# Sheet1.net
KiCad netlist of a schematic drawn in Altium Designer
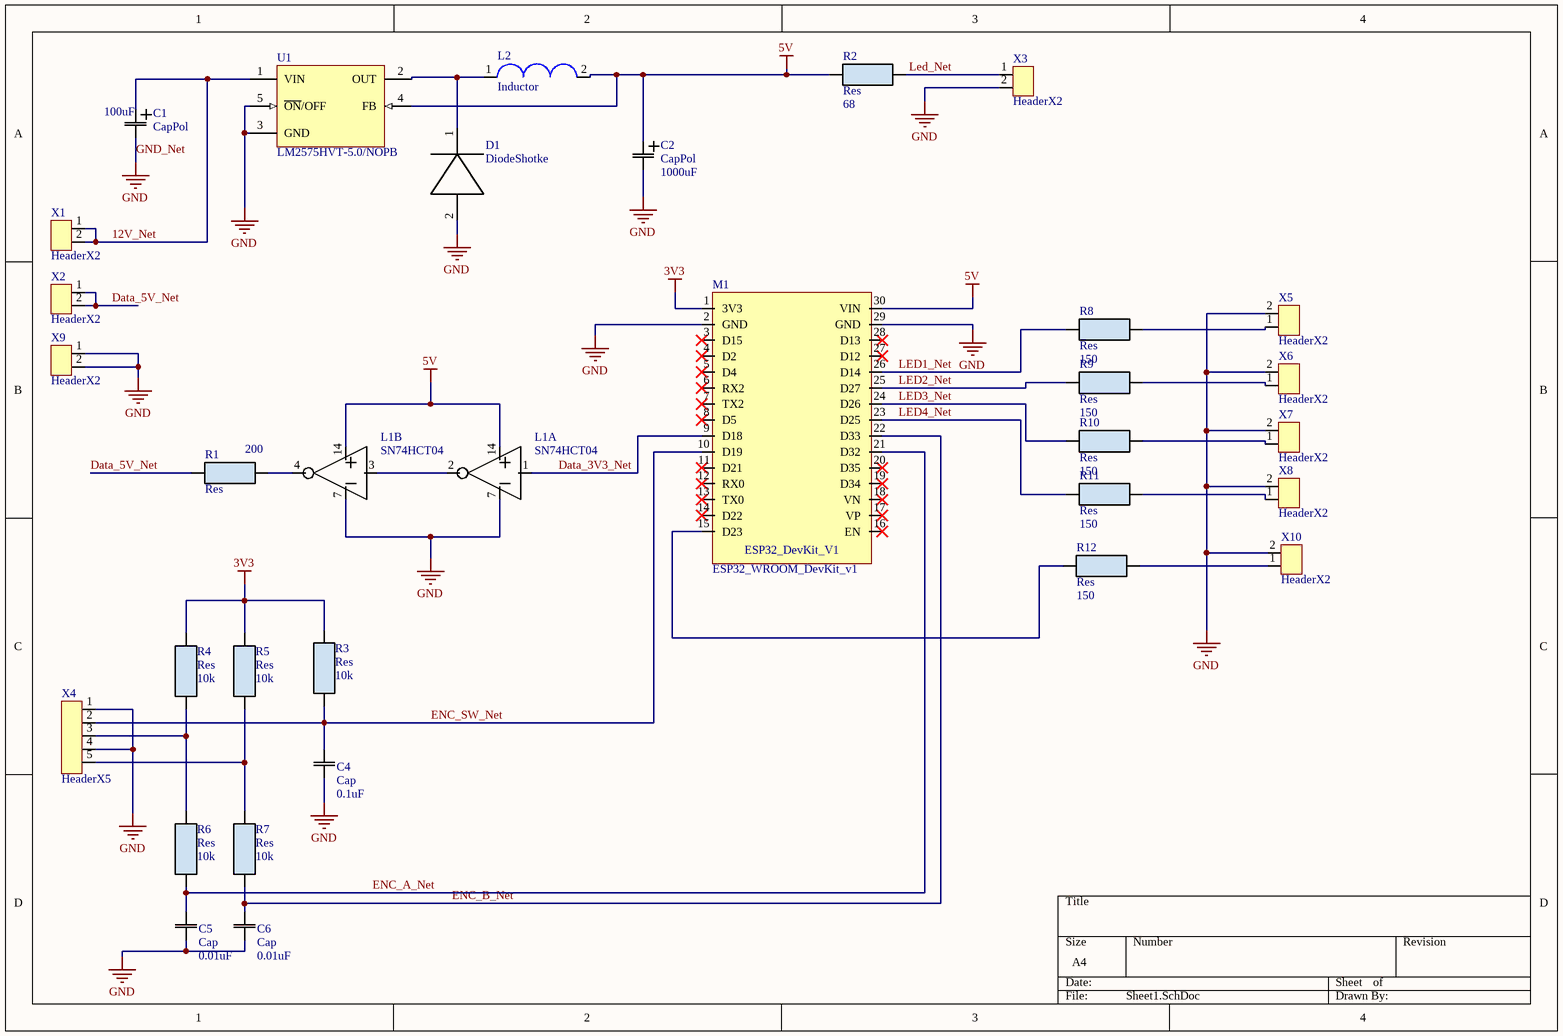
[diagram p0: Sheet1.SchDoc]

(export (version "E")
  (design (tool "Eeschema 10.0.6"))
  (components
    (comp (ref "C1")
      (value "CapPol")
      (footprint "CAP 8x7")
      (fields (field (name "ALTIUM_VALUE") "100uF"))
      (libsource (lib "KiShiVi") (part "CapPol"))
    )
    (comp (ref "C2")
      (value "CapPol")
      (footprint "CAP 10x12.5")
      (fields (field (name "ALTIUM_VALUE") "1000uF"))
      (libsource (lib "KiShiVi") (part "CapPol"))
    )
    (comp (ref "C4")
      (value "Cap")
      (footprint "Cap K73-17 0.1uF 100V 5-10%")
      (fields (field (name "ALTIUM_VALUE") "0.1uF"))
      (libsource (lib "KiShiVi") (part "Cap"))
    )
    (comp (ref "C5")
      (value "Cap")
      (footprint "Cap K73-17 0.01uF 100V 5-10%")
      (fields (field (name "ALTIUM_VALUE") "0.01uF"))
      (libsource (lib "KiShiVi") (part "Cap"))
    )
    (comp (ref "C6")
      (value "Cap")
      (footprint "Cap K73-17 0.01uF 100V 5-10%")
      (fields (field (name "ALTIUM_VALUE") "0.01uF"))
      (libsource (lib "KiShiVi") (part "Cap"))
    )
    (comp (ref "D1")
      (value "DiodeShotke")
      (footprint "DIODE_SHOTKE")
      (libsource (lib "KiShiVi") (part "DiodeShotke"))
    )
    (comp (ref "L1") (value "SN74HCT04") (footprint "DIP-14") (libsource (lib "KiShiVi") (part "SN74HCT04")))
    (comp (ref "L2")
      (value "Inductor")
      (footprint "RLB0912-101KL")
      (libsource (lib "KiShiVi") (part "Inductor"))
    )
    (comp (ref "M1")
      (value "ESP32_WROOM_DevKit_v1")
      (footprint "ESP32_WROOM_DevKit_v1")
      (libsource (lib "KiShiVi") (part "ESP32_WROOM_DevKit_v1"))
    )
    (comp (ref "R1")
      (value "Res")
      (footprint "Resistor MF-25")
      (fields (field (name "ALTIUM_VALUE") "200"))
      (libsource (lib "") (part "Res_1"))
    )
    (comp (ref "R2")
      (value "Res")
      (footprint "Resistor MF-25")
      (fields (field (name "ALTIUM_VALUE") "68"))
      (libsource (lib "") (part "Res_1"))
    )
    (comp (ref "R3")
      (value "Res")
      (footprint "Resistor MF-25")
      (fields (field (name "ALTIUM_VALUE") "10k"))
      (libsource (lib "KiShiVi") (part "Res"))
    )
    (comp (ref "R4")
      (value "Res")
      (footprint "Resistor MF-25")
      (fields (field (name "ALTIUM_VALUE") "10k"))
      (libsource (lib "KiShiVi") (part "Res"))
    )
    (comp (ref "R5")
      (value "Res")
      (footprint "Resistor MF-25")
      (fields (field (name "ALTIUM_VALUE") "10k"))
      (libsource (lib "KiShiVi") (part "Res"))
    )
    (comp (ref "R6")
      (value "Res")
      (footprint "Resistor MF-25")
      (fields (field (name "ALTIUM_VALUE") "10k"))
      (libsource (lib "KiShiVi") (part "Res"))
    )
    (comp (ref "R7")
      (value "Res")
      (footprint "Resistor MF-25")
      (fields (field (name "ALTIUM_VALUE") "10k"))
      (libsource (lib "KiShiVi") (part "Res"))
    )
    (comp (ref "R8")
      (value "Res")
      (footprint "Resistor MF-25")
      (fields (field (name "ALTIUM_VALUE") "150"))
      (libsource (lib "") (part "Res_1"))
    )
    (comp (ref "R9")
      (value "Res")
      (footprint "Resistor MF-25")
      (fields (field (name "ALTIUM_VALUE") "150"))
      (libsource (lib "") (part "Res_1"))
    )
    (comp (ref "R10")
      (value "Res")
      (footprint "Resistor MF-25")
      (fields (field (name "ALTIUM_VALUE") "150"))
      (libsource (lib "") (part "Res_1"))
    )
    (comp (ref "R11")
      (value "Res")
      (footprint "Resistor MF-25")
      (fields (field (name "ALTIUM_VALUE") "150"))
      (libsource (lib "") (part "Res_1"))
    )
    (comp (ref "R12")
      (value "Res")
      (footprint "Resistor MF-25")
      (fields (field (name "ALTIUM_VALUE") "150"))
      (libsource (lib "") (part "Res_1"))
    )
    (comp (ref "U1")
      (value "LM2575HVT-5.0/NOPB")
      (footprint "KC0005A")
      (description "SIMPLE SWITCHER® 1A Step-Down Voltage Regulator, 5-pin TO-220, Pb-Free")
      (fields (field (name "MANUFACTURER") "Texas Instruments"))
      (libsource (lib "Altium Content Vault") (part "PM-REG-LM2575HVT-12"))
    )
    (comp (ref "X1")
      (value "HeaderX2")
      (footprint "TERMINAL_X2_5MM")
      (libsource (lib "") (part "HeaderX2_2"))
    )
    (comp (ref "X2")
      (value "HeaderX2")
      (footprint "TERMINAL_X2_5MM")
      (libsource (lib "") (part "HeaderX2_2"))
    )
    (comp (ref "X3") (value "HeaderX2") (footprint "HEADERX2") (libsource (lib "") (part "HeaderX2_1")))
    (comp (ref "X4") (value "HeaderX5") (footprint "HeaderX5") (libsource (lib "KiShiVi") (part "HeaderX5")))
    (comp (ref "X5") (value "HeaderX2") (footprint "HEADERX2") (libsource (lib "KiShiVi") (part "HeaderX2")))
    (comp (ref "X6") (value "HeaderX2") (footprint "HEADERX2") (libsource (lib "KiShiVi") (part "HeaderX2")))
    (comp (ref "X7") (value "HeaderX2") (footprint "HEADERX2") (libsource (lib "KiShiVi") (part "HeaderX2")))
    (comp (ref "X8") (value "HeaderX2") (footprint "HEADERX2") (libsource (lib "KiShiVi") (part "HeaderX2")))
    (comp (ref "X9")
      (value "HeaderX2")
      (footprint "TERMINAL_X2_5MM")
      (libsource (lib "") (part "HeaderX2_2"))
    )
    (comp (ref "X10") (value "HeaderX2") (footprint "HEADERX2") (libsource (lib "KiShiVi") (part "HeaderX2")))
  )
  (nets
    (net (code "1") (name "/12V_Net") (class "Default")
      (node (ref "C1") (pin "1") (pinfunction "1_1") (pintype "passive"))
      (node (ref "U1") (pin "1") (pinfunction "VIN_1") (pintype "power_in"))
      (node (ref "X1") (pin "1") (pinfunction "1_1") (pintype "passive"))
      (node (ref "X1") (pin "2") (pinfunction "2_2") (pintype "passive"))
    )
    (net (code "2") (name "/Data_3V3_Net") (class "Default")
      (node (ref "L1") (pin "1") (pinfunction "A_1") (pintype "passive"))
      (node (ref "M1") (pin "9") (pinfunction "D18_9") (pintype "passive"))
    )
    (net (code "3") (name "/Data_5V_Net") (class "Default")
      (node (ref "R1") (pin "1") (pinfunction "1_1") (pintype "passive"))
      (node (ref "X2") (pin "1") (pinfunction "1_1") (pintype "passive"))
      (node (ref "X2") (pin "2") (pinfunction "2_2") (pintype "passive"))
    )
    (net (code "4") (name "/ENC_A_Net") (class "Default")
      (node (ref "C5") (pin "2") (pinfunction "2_2") (pintype "passive"))
      (node (ref "M1") (pin "21") (pinfunction "D32_21") (pintype "passive"))
      (node (ref "R6") (pin "1") (pinfunction "1_1") (pintype "passive"))
    )
    (net (code "5") (name "/ENC_B_Net") (class "Default")
      (node (ref "C6") (pin "2") (pinfunction "2_2") (pintype "passive"))
      (node (ref "M1") (pin "22") (pinfunction "D33_22") (pintype "passive"))
      (node (ref "R7") (pin "1") (pinfunction "1_1") (pintype "passive"))
    )
    (net (code "6") (name "/ENC_SW_Net") (class "Default")
      (node (ref "C4") (pin "2") (pinfunction "2_2") (pintype "passive"))
      (node (ref "M1") (pin "10") (pinfunction "D19_10") (pintype "passive"))
      (node (ref "R3") (pin "1") (pinfunction "1_1") (pintype "passive"))
      (node (ref "X4") (pin "2") (pinfunction "2_2") (pintype "passive"))
    )
    (net (code "7") (name "/LED1_Net") (class "Default")
      (node (ref "M1") (pin "26") (pinfunction "D14_26") (pintype "passive"))
      (node (ref "R8") (pin "1") (pinfunction "1_1") (pintype "passive"))
    )
    (net (code "8") (name "/LED2_Net") (class "Default")
      (node (ref "M1") (pin "25") (pinfunction "D27_25") (pintype "passive"))
      (node (ref "R9") (pin "1") (pinfunction "1_1") (pintype "passive"))
    )
    (net (code "9") (name "/LED3_Net") (class "Default")
      (node (ref "M1") (pin "24") (pinfunction "D26_24") (pintype "passive"))
      (node (ref "R10") (pin "1") (pinfunction "1_1") (pintype "passive"))
    )
    (net (code "10") (name "/LED4_Net") (class "Default")
      (node (ref "M1") (pin "23") (pinfunction "D25_23") (pintype "passive"))
      (node (ref "R11") (pin "1") (pinfunction "1_1") (pintype "passive"))
    )
    (net (code "11") (name "/Led_Net") (class "Default")
      (node (ref "R2") (pin "2") (pinfunction "2_2") (pintype "passive"))
      (node (ref "X3") (pin "1") (pinfunction "1_1") (pintype "passive"))
    )
    (net (code "12") (name "3V3") (class "Default")
      (node (ref "M1") (pin "1") (pinfunction "3V3_1") (pintype "passive"))
      (node (ref "R3") (pin "2") (pinfunction "2_2") (pintype "passive"))
      (node (ref "R4") (pin "2") (pinfunction "2_2") (pintype "passive"))
      (node (ref "R5") (pin "2") (pinfunction "2_2") (pintype "passive"))
    )
    (net (code "13") (name "5V") (class "Default")
      (node (ref "C2") (pin "1") (pinfunction "1_1") (pintype "passive"))
      (node (ref "L1") (pin "14") (pinfunction "3_14") (pintype "passive"))
      (node (ref "L2") (pin "2") (pinfunction "6_2") (pintype "passive"))
      (node (ref "M1") (pin "30") (pinfunction "VIN_30") (pintype "passive"))
      (node (ref "R2") (pin "1") (pinfunction "1_1") (pintype "passive"))
      (node (ref "U1") (pin "4") (pinfunction "FB_4") (pintype "input"))
    )
    (net (code "14") (name "GND") (class "Default")
      (node (ref "C1") (pin "2") (pinfunction "2_2") (pintype "passive"))
      (node (ref "C2") (pin "2") (pinfunction "2_2") (pintype "passive"))
      (node (ref "C4") (pin "1") (pinfunction "1_1") (pintype "passive"))
      (node (ref "C5") (pin "1") (pinfunction "1_1") (pintype "passive"))
      (node (ref "C6") (pin "1") (pinfunction "1_1") (pintype "passive"))
      (node (ref "D1") (pin "2") (pinfunction "8_2") (pintype "passive"))
      (node (ref "L1") (pin "7") (pinfunction "4_7") (pintype "passive"))
      (node (ref "M1") (pin "2") (pinfunction "GND_2") (pintype "passive"))
      (node (ref "M1") (pin "29") (pinfunction "GND_29") (pintype "passive"))
      (node (ref "U1") (pin "3") (pinfunction "GND_3") (pintype "power_in"))
      (node (ref "U1") (pin "5") (pinfunction "~{ON}/OFF_5") (pintype "input"))
      (node (ref "X10") (pin "2") (pinfunction "2_2") (pintype "passive"))
      (node (ref "X3") (pin "2") (pinfunction "2_2") (pintype "passive"))
      (node (ref "X4") (pin "1") (pinfunction "BTN_GND_1") (pintype "passive"))
      (node (ref "X4") (pin "4") (pinfunction "4_4") (pintype "passive"))
      (node (ref "X5") (pin "2") (pinfunction "2_2") (pintype "passive"))
      (node (ref "X6") (pin "2") (pinfunction "2_2") (pintype "passive"))
      (node (ref "X7") (pin "2") (pinfunction "2_2") (pintype "passive"))
      (node (ref "X8") (pin "2") (pinfunction "2_2") (pintype "passive"))
      (node (ref "X9") (pin "1") (pinfunction "1_1") (pintype "passive"))
      (node (ref "X9") (pin "2") (pinfunction "2_2") (pintype "passive"))
    )
    (net (code "15") (name "Net-(D1-7)") (class "Default")
      (node (ref "D1") (pin "1") (pinfunction "7_1") (pintype "passive"))
      (node (ref "L2") (pin "1") (pinfunction "5_1") (pintype "passive"))
      (node (ref "U1") (pin "2") (pinfunction "OUT_2") (pintype "power_in"))
    )
    (net (code "16") (name "Net-(L1A-Y)") (class "Default")
      (node (ref "L1") (pin "2") (pinfunction "Y_2") (pintype "passive"))
      (node (ref "L1") (pin "3") (pinfunction "A_3") (pintype "passive"))
    )
    (net (code "17") (name "Net-(L1B-Y)") (class "Default")
      (node (ref "L1") (pin "4") (pinfunction "Y_4") (pintype "passive"))
      (node (ref "R1") (pin "2") (pinfunction "2_2") (pintype "passive"))
    )
    (net (code "18") (name "Net-(M1-D23)") (class "Default")
      (node (ref "M1") (pin "15") (pinfunction "D23_15") (pintype "passive"))
      (node (ref "R12") (pin "1") (pinfunction "1_1") (pintype "passive"))
    )
    (net (code "19") (name "Net-(R4-Pad1)") (class "Default")
      (node (ref "R4") (pin "1") (pinfunction "1_1") (pintype "passive"))
      (node (ref "R6") (pin "2") (pinfunction "2_2") (pintype "passive"))
      (node (ref "X4") (pin "3") (pinfunction "3_3") (pintype "passive"))
    )
    (net (code "20") (name "Net-(R5-Pad1)") (class "Default")
      (node (ref "R5") (pin "1") (pinfunction "1_1") (pintype "passive"))
      (node (ref "R7") (pin "2") (pinfunction "2_2") (pintype "passive"))
      (node (ref "X4") (pin "5") (pinfunction "5_5") (pintype "passive"))
    )
    (net (code "21") (name "Net-(R8-Pad2)") (class "Default")
      (node (ref "R8") (pin "2") (pinfunction "2_2") (pintype "passive"))
      (node (ref "X5") (pin "1") (pinfunction "1_1") (pintype "passive"))
    )
    (net (code "22") (name "Net-(R9-Pad2)") (class "Default")
      (node (ref "R9") (pin "2") (pinfunction "2_2") (pintype "passive"))
      (node (ref "X6") (pin "1") (pinfunction "1_1") (pintype "passive"))
    )
    (net (code "23") (name "Net-(R10-Pad2)") (class "Default")
      (node (ref "R10") (pin "2") (pinfunction "2_2") (pintype "passive"))
      (node (ref "X7") (pin "1") (pinfunction "1_1") (pintype "passive"))
    )
    (net (code "24") (name "Net-(R11-Pad2)") (class "Default")
      (node (ref "R11") (pin "2") (pinfunction "2_2") (pintype "passive"))
      (node (ref "X8") (pin "1") (pinfunction "1_1") (pintype "passive"))
    )
    (net (code "25") (name "Net-(R12-Pad2)") (class "Default")
      (node (ref "R12") (pin "2") (pinfunction "2_2") (pintype "passive"))
      (node (ref "X10") (pin "1") (pinfunction "1_1") (pintype "passive"))
    )
    (net (code "26") (name "unconnected-(M1-D2-Pad4)") (class "Default")
      (node (ref "M1") (pin "4") (pinfunction "D2_4") (pintype "passive+no_connect"))
    )
    (net (code "27") (name "unconnected-(M1-D4-Pad5)") (class "Default")
      (node (ref "M1") (pin "5") (pinfunction "D4_5") (pintype "passive+no_connect"))
    )
    (net (code "28") (name "unconnected-(M1-D5-Pad8)") (class "Default")
      (node (ref "M1") (pin "8") (pinfunction "D5_8") (pintype "passive+no_connect"))
    )
    (net (code "29") (name "unconnected-(M1-D12-Pad27)") (class "Default")
      (node (ref "M1") (pin "27") (pinfunction "D12_27") (pintype "passive+no_connect"))
    )
    (net (code "30") (name "unconnected-(M1-D13-Pad28)") (class "Default")
      (node (ref "M1") (pin "28") (pinfunction "D13_28") (pintype "passive+no_connect"))
    )
    (net (code "31") (name "unconnected-(M1-D15-Pad3)") (class "Default")
      (node (ref "M1") (pin "3") (pinfunction "D15_3") (pintype "passive+no_connect"))
    )
    (net (code "32") (name "unconnected-(M1-D21-Pad11)") (class "Default")
      (node (ref "M1") (pin "11") (pinfunction "D21_11") (pintype "passive+no_connect"))
    )
    (net (code "33") (name "unconnected-(M1-D22-Pad14)") (class "Default")
      (node (ref "M1") (pin "14") (pinfunction "D22_14") (pintype "passive+no_connect"))
    )
    (net (code "34") (name "unconnected-(M1-D34-Pad19)") (class "Default")
      (node (ref "M1") (pin "19") (pinfunction "D34_19") (pintype "passive+no_connect"))
    )
    (net (code "35") (name "unconnected-(M1-D35-Pad20)") (class "Default")
      (node (ref "M1") (pin "20") (pinfunction "D35_20") (pintype "passive+no_connect"))
    )
    (net (code "36") (name "unconnected-(M1-EN-Pad16)") (class "Default")
      (node (ref "M1") (pin "16") (pinfunction "EN_16") (pintype "passive+no_connect"))
    )
    (net (code "37") (name "unconnected-(M1-RX0-Pad12)") (class "Default")
      (node (ref "M1") (pin "12") (pinfunction "RX0_12") (pintype "passive+no_connect"))
    )
    (net (code "38") (name "unconnected-(M1-RX2-Pad6)") (class "Default")
      (node (ref "M1") (pin "6") (pinfunction "RX2_6") (pintype "passive+no_connect"))
    )
    (net (code "39") (name "unconnected-(M1-TX0-Pad13)") (class "Default")
      (node (ref "M1") (pin "13") (pinfunction "TX0_13") (pintype "passive+no_connect"))
    )
    (net (code "40") (name "unconnected-(M1-TX2-Pad7)") (class "Default")
      (node (ref "M1") (pin "7") (pinfunction "TX2_7") (pintype "passive+no_connect"))
    )
    (net (code "41") (name "unconnected-(M1-VN-Pad18)") (class "Default")
      (node (ref "M1") (pin "18") (pinfunction "VN_18") (pintype "passive+no_connect"))
    )
    (net (code "42") (name "unconnected-(M1-VP-Pad17)") (class "Default")
      (node (ref "M1") (pin "17") (pinfunction "VP_17") (pintype "passive+no_connect"))
    )
  )
)
